# Main.net
KiCad netlist of a schematic drawn in Altium Designer
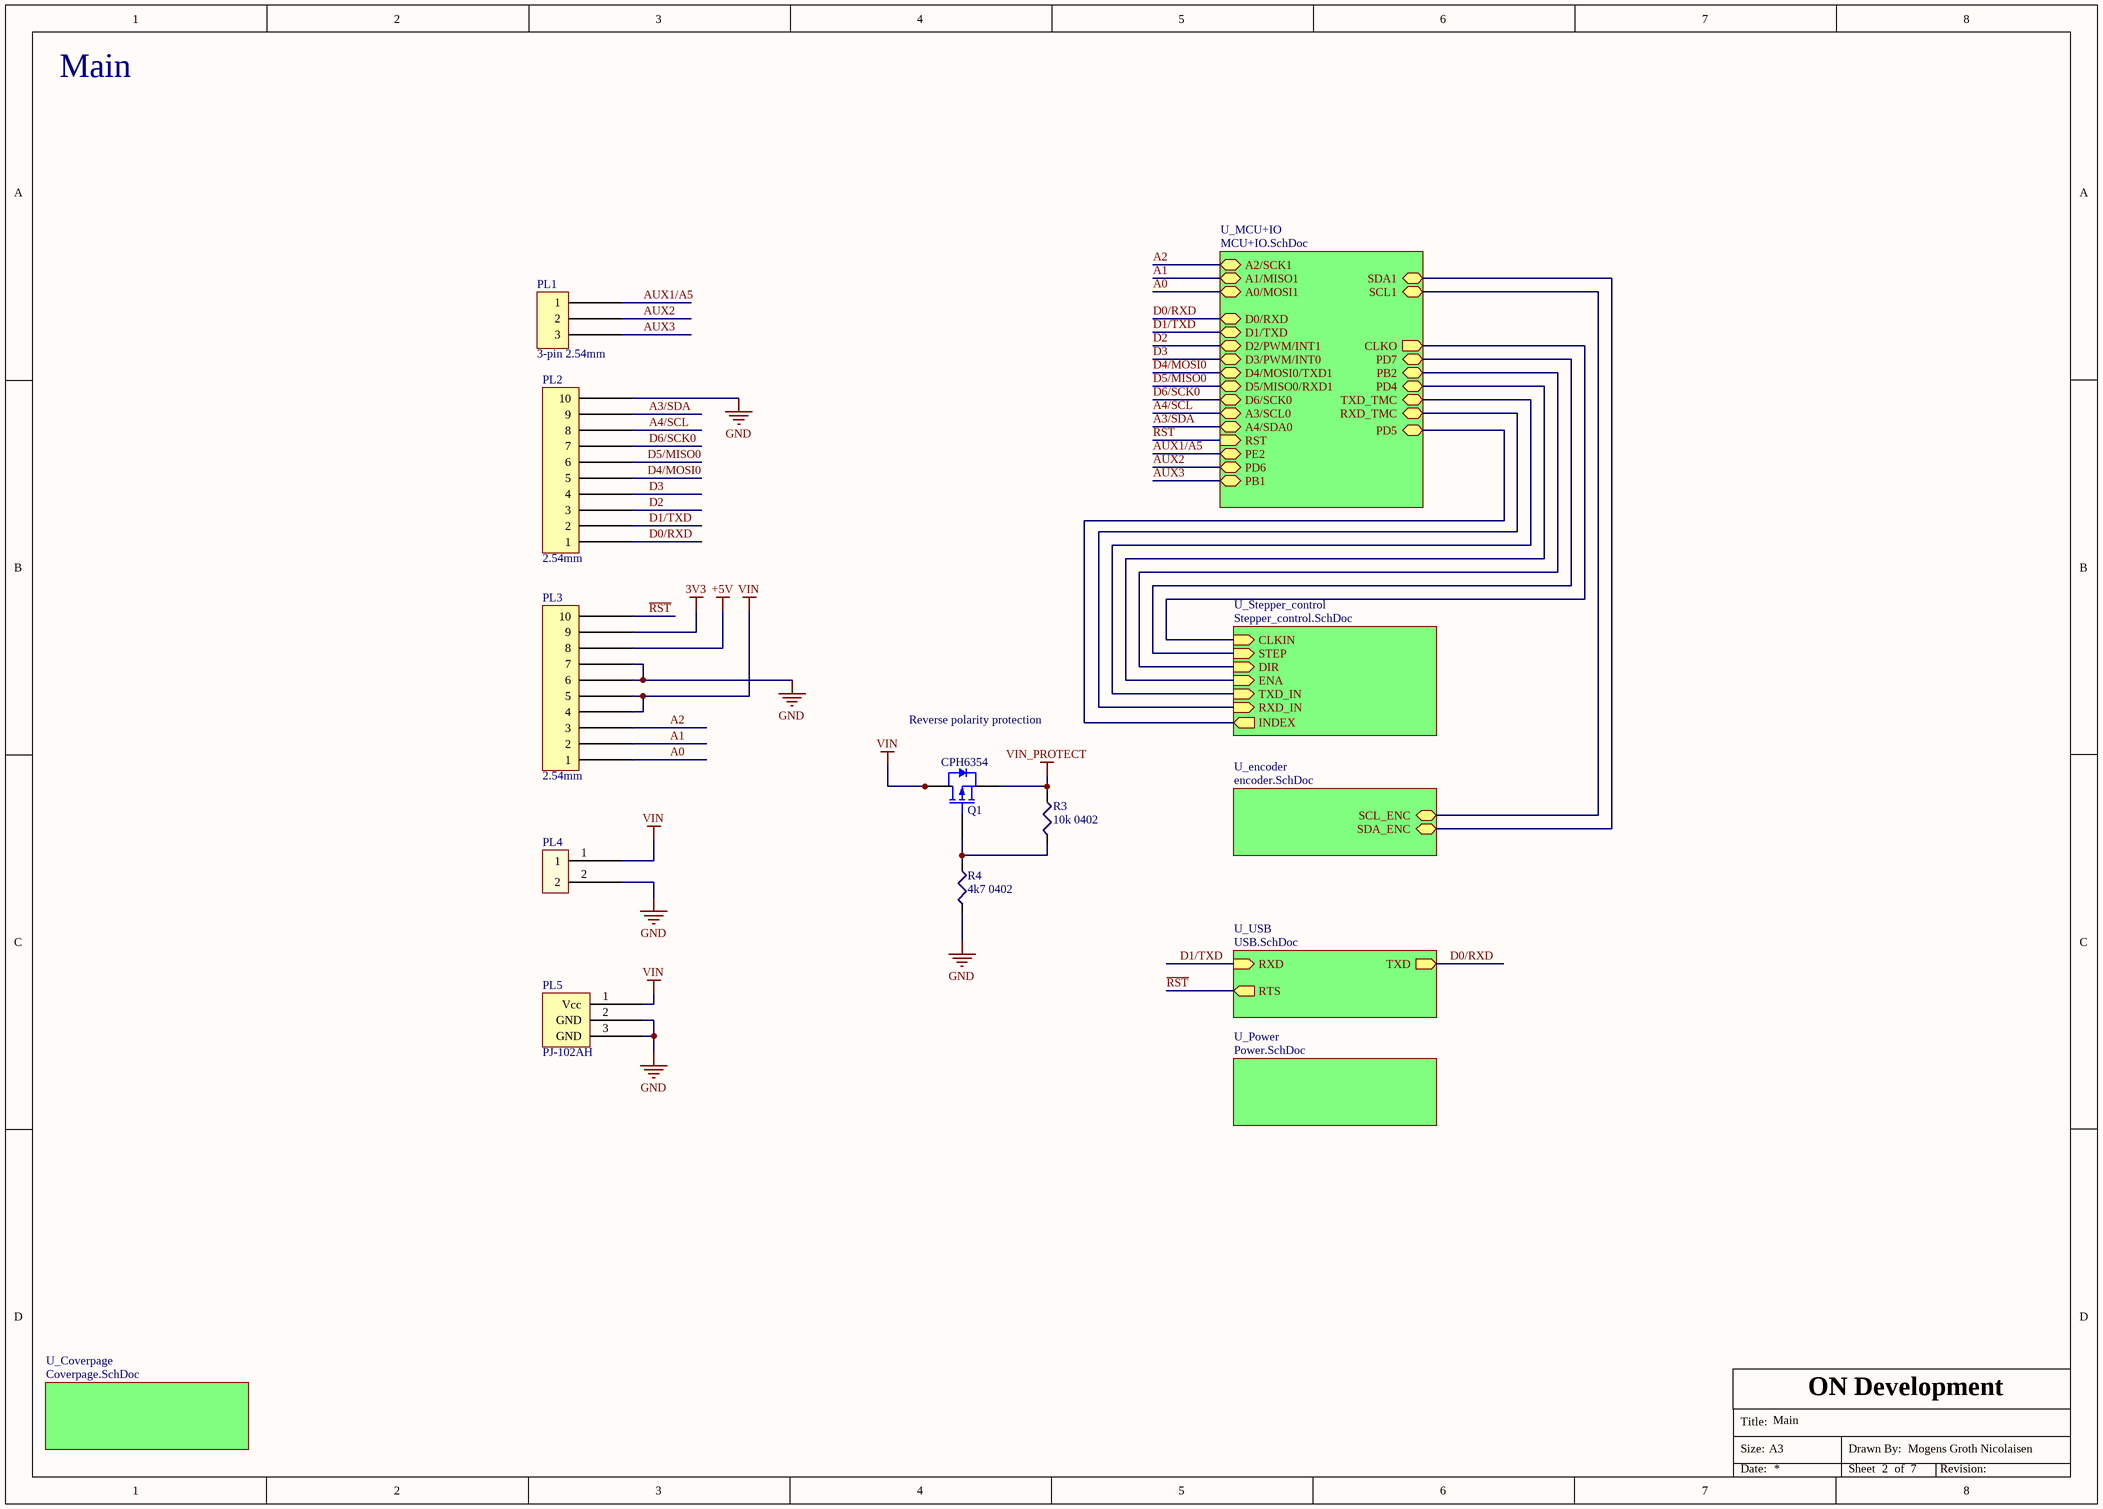
[diagram p0: Main.SchDoc]

(export (version "E")
  (design (tool "Eeschema 10.0.6"))
  (components
    (comp (ref "PL1")
      (value "3-pin 2.54mm")
      (footprint "3-pin 2.54mm header")
      (description "Pin header 3-pin 2.54mm male")
      (fields (field (name "MFG. PART NUMBER") "DS1021-1*3SF1-1"))
      (libsource (lib "ON Development Vault") (part "CMP-003-0018-1"))
    )
    (comp (ref "PL2")
      (value "2.54mm")
      (footprint "10-pin female 2.54mm")
      (description "Pin header 10-pin 2.54mm female")
      (fields (field (name "MFG. PART NUMBER") "DS1023-1*10S21"))
      (libsource (lib "ON Development Vault") (part "10-pin header"))
    )
    (comp (ref "PL3")
      (value "2.54mm")
      (footprint "10-pin female 2.54mm")
      (description "Pin header 10-pin 2.54mm female")
      (fields (field (name "MFG. PART NUMBER") "DS1023-1*10S21"))
      (libsource (lib "ON Development Vault") (part "10-pin header"))
    )
    (comp (ref "PL4")
      (value "2pin Terminal block 5.08mm")
      (footprint "5mm header")
      (description "PCB terminal block, angled 90°; 5mm, 2-way, 1.5mm2")
      (fields (field (name "MFG. PART NUMBER") "DG301-5.0-02P-11-00A(H)"))
      (libsource (lib "ON Development Vault") (part "Header 2-way"))
    )
    (comp (ref "PL5")
      (value "PJ-102AH")
      (footprint "PJ-102AH")
      (description "CONN PWR JACK 2X5.5MM SOLDER")
      (libsource (lib "ON Development Vault") (part "PJ-102AH"))
    )
    (comp (ref "Q1")
      (value "CPH6354")
      (footprint "SOT95P280X95-6N")
      (description "MOSFET P-CH 60V 4A CPH6")
      (fields (field (name "MFG. PART NUMBER") "CPH6354-TL-W"))
      (libsource (lib "ON Development Vault") (part "P-channel CPH6354"))
    )
    (comp (ref "R3")
      (value "10k 0402")
      (footprint "RES_0402")
      (description "RES SMD 10K OHM 1% 1/16W 0402")
      (fields (field (name "POWER") "1/16 W") (field (name "TOLERANCE") "1 %"))
      (libsource (lib "ON Development Vault") (part "Resistor"))
    )
    (comp (ref "R4")
      (value "4k7 0402")
      (footprint "RES_0402")
      (description "RES SMD 4.7K OHM 1% 1/16W 0402")
      (fields (field (name "POWER") "1/16W") (field (name "TOLERANCE") "1"))
      (libsource (lib "ON Development Vault") (part "Resistor"))
    )
  )
  (nets
    (net (code "1") (name "+5V") (class "Default")
      (node (ref "PL3") (pin "8") (pinfunction "8_8") (pintype "passive"))
    )
    (net (code "2") (name "/A0") (class "Default")
      (node (ref "PL3") (pin "1") (pinfunction "1_1") (pintype "passive"))
    )
    (net (code "3") (name "/A1") (class "Default")
      (node (ref "PL3") (pin "2") (pinfunction "2_2") (pintype "passive"))
    )
    (net (code "4") (name "/A2") (class "Default")
      (node (ref "PL3") (pin "3") (pinfunction "3_3") (pintype "passive"))
    )
    (net (code "5") (name "/A3{slash}SDA") (class "Default")
      (node (ref "PL2") (pin "9") (pinfunction "9_9") (pintype "passive"))
    )
    (net (code "6") (name "/A4{slash}SCL") (class "Default")
      (node (ref "PL2") (pin "8") (pinfunction "8_8") (pintype "passive"))
    )
    (net (code "7") (name "/AUX1{slash}A5") (class "Default")
      (node (ref "PL1") (pin "1") (pinfunction "1_1") (pintype "passive"))
    )
    (net (code "8") (name "/AUX2") (class "Default")
      (node (ref "PL1") (pin "2") (pinfunction "2_2") (pintype "passive"))
    )
    (net (code "9") (name "/AUX3") (class "Default")
      (node (ref "PL1") (pin "3") (pinfunction "3_3") (pintype "passive"))
    )
    (net (code "11") (name "/D0{slash}RXD") (class "Default")
      (node (ref "PL2") (pin "1") (pinfunction "1_1") (pintype "passive"))
    )
    (net (code "12") (name "/D1{slash}TXD") (class "Default")
      (node (ref "PL2") (pin "2") (pinfunction "2_2") (pintype "passive"))
    )
    (net (code "13") (name "/D2") (class "Default")
      (node (ref "PL2") (pin "3") (pinfunction "3_3") (pintype "passive"))
    )
    (net (code "14") (name "/D3") (class "Default")
      (node (ref "PL2") (pin "4") (pinfunction "4_4") (pintype "passive"))
    )
    (net (code "15") (name "/D4{slash}MOSI0") (class "Default")
      (node (ref "PL2") (pin "5") (pinfunction "5_5") (pintype "passive"))
    )
    (net (code "16") (name "/D5{slash}MISO0") (class "Default")
      (node (ref "PL2") (pin "6") (pinfunction "6_6") (pintype "passive"))
    )
    (net (code "17") (name "/D6{slash}SCK0") (class "Default")
      (node (ref "PL2") (pin "7") (pinfunction "7_7") (pintype "passive"))
    )
    (net (code "26") (name "/~{RST}") (class "Default")
      (node (ref "PL3") (pin "10") (pinfunction "10_10") (pintype "passive"))
    )
    (net (code "27") (name "3V3") (class "Default")
      (node (ref "PL3") (pin "9") (pinfunction "9_9") (pintype "passive"))
    )
    (net (code "28") (name "GND") (class "Default")
      (node (ref "PL2") (pin "10") (pinfunction "10_10") (pintype "passive"))
      (node (ref "PL3") (pin "6") (pinfunction "6_6") (pintype "passive"))
      (node (ref "PL3") (pin "7") (pinfunction "7_7") (pintype "passive"))
      (node (ref "PL4") (pin "2") (pinfunction "2_2") (pintype "passive"))
      (node (ref "PL5") (pin "2") (pinfunction "GND_2") (pintype "passive"))
      (node (ref "PL5") (pin "3") (pinfunction "GND_3") (pintype "passive"))
      (node (ref "R4") (pin "1") (pinfunction "1_1") (pintype "passive"))
    )
    (net (code "29") (name "Net-(Q1-GATE)") (class "Default")
      (node (ref "Q1") (pin "3") (pinfunction "GATE_3") (pintype "passive"))
      (node (ref "R3") (pin "1") (pinfunction "1_1") (pintype "passive"))
      (node (ref "R4") (pin "2") (pinfunction "2_2") (pintype "passive"))
    )
    (net (code "30") (name "VIN") (class "Default")
      (node (ref "PL3") (pin "4") (pinfunction "4_4") (pintype "passive"))
      (node (ref "PL3") (pin "5") (pinfunction "5_5") (pintype "passive"))
      (node (ref "PL4") (pin "1") (pinfunction "1_1") (pintype "passive"))
      (node (ref "PL5") (pin "1") (pinfunction "Vcc_1") (pintype "passive"))
      (node (ref "Q1") (pin "1") (pinfunction "DRAIN_1") (pintype "passive"))
      (node (ref "Q1") (pin "2") (pinfunction "DRAIN_2") (pintype "passive"))
      (node (ref "Q1") (pin "5") (pinfunction "DRAIN_5") (pintype "passive"))
      (node (ref "Q1") (pin "6") (pinfunction "DRAIN_6") (pintype "passive"))
    )
    (net (code "31") (name "VIN_PROTECT") (class "Default")
      (node (ref "Q1") (pin "4") (pinfunction "SOURCE_4") (pintype "passive"))
      (node (ref "R3") (pin "2") (pinfunction "2_2") (pintype "passive"))
    )
  )
)
